# MCU.net
KiCad netlist of a schematic drawn in Altium Designer
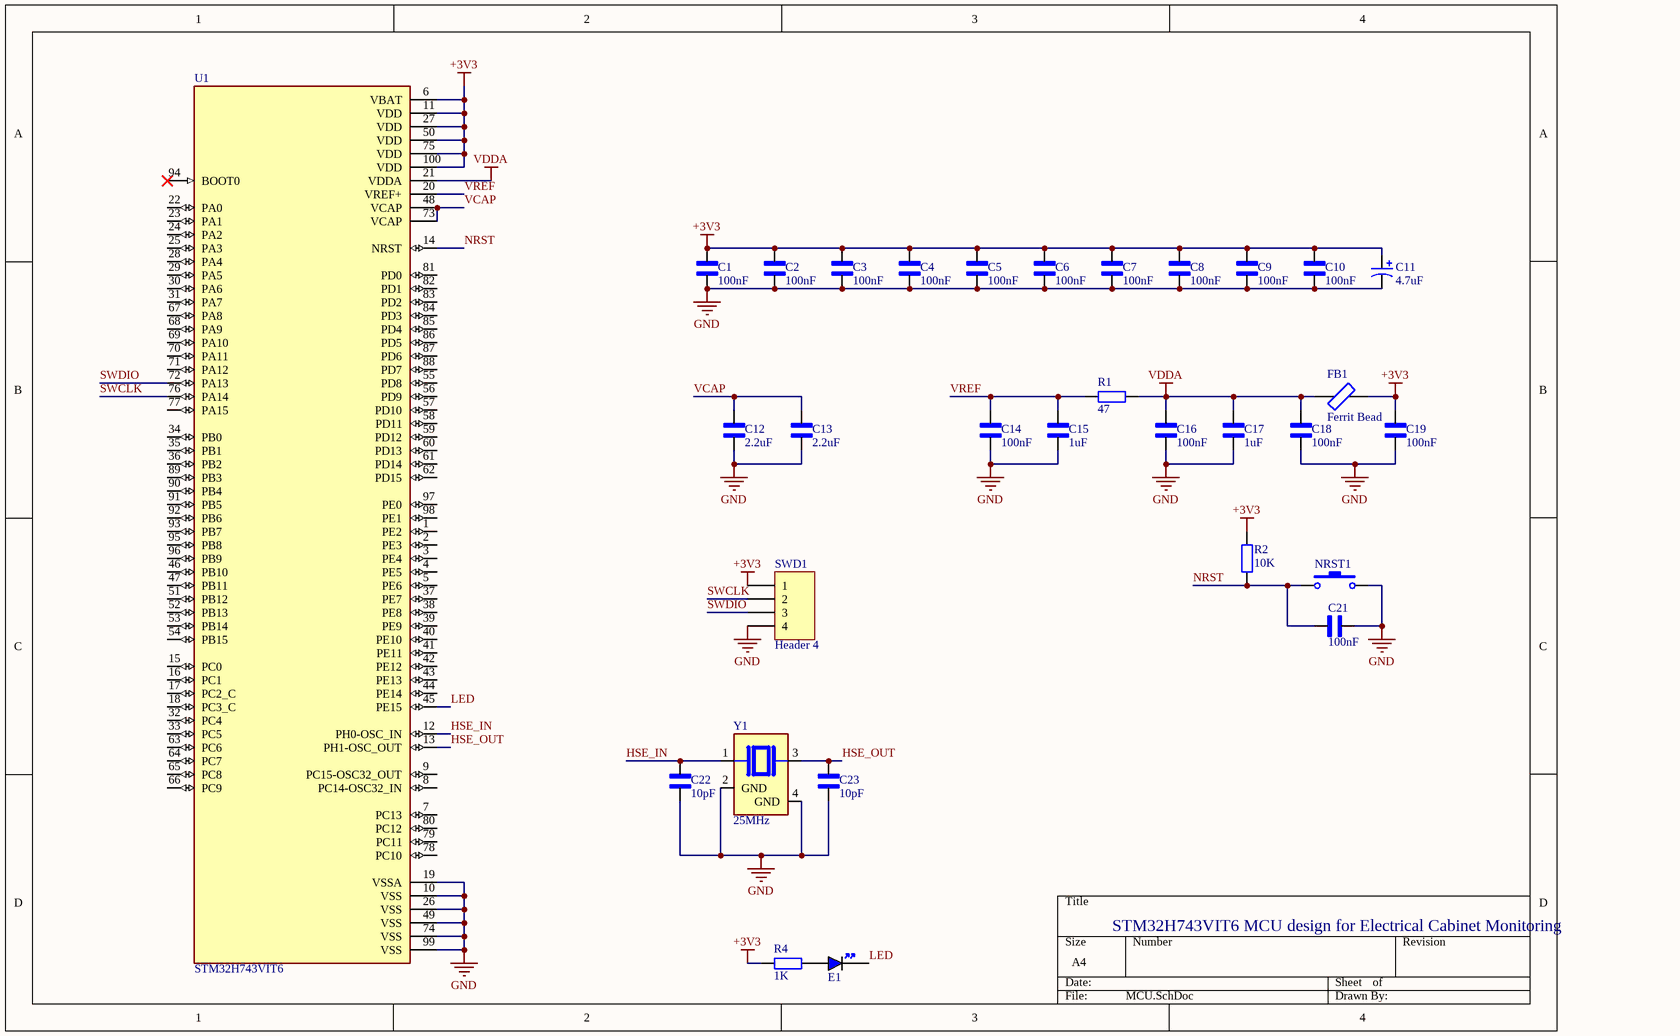
[diagram p0: MCU.SchDoc]

(export (version "E")
  (design (tool "Eeschema 10.0.6"))
  (components
    (comp (ref "C1")
      (value "100nF")
      (footprint "CAPC2012X145N")
      (description "39 pF Â±2% 200V Ceramic Capacitor C0G, NP0 0805 (2012 Metric)")
      (fields (field (name "MF") "Vishay Vitramon") (field (name "MP") "VJ0805A390GXCAP"))
      (libsource (lib "VJ0805A390GXCAP") (part "VJ0805A390GXCAP"))
    )
    (comp (ref "C2")
      (value "100nF")
      (footprint "CAPC2012X145N")
      (description "39 pF Â±2% 200V Ceramic Capacitor C0G, NP0 0805 (2012 Metric)")
      (fields (field (name "MF") "Vishay Vitramon") (field (name "MP") "VJ0805A390GXCAP"))
      (libsource (lib "VJ0805A390GXCAP") (part "VJ0805A390GXCAP"))
    )
    (comp (ref "C3")
      (value "100nF")
      (footprint "CAPC2012X145N")
      (description "39 pF Â±2% 200V Ceramic Capacitor C0G, NP0 0805 (2012 Metric)")
      (fields (field (name "MF") "Vishay Vitramon") (field (name "MP") "VJ0805A390GXCAP"))
      (libsource (lib "VJ0805A390GXCAP") (part "VJ0805A390GXCAP"))
    )
    (comp (ref "C4")
      (value "100nF")
      (footprint "CAPC2012X145N")
      (description "39 pF Â±2% 200V Ceramic Capacitor C0G, NP0 0805 (2012 Metric)")
      (fields (field (name "MF") "Vishay Vitramon") (field (name "MP") "VJ0805A390GXCAP"))
      (libsource (lib "VJ0805A390GXCAP") (part "VJ0805A390GXCAP"))
    )
    (comp (ref "C5")
      (value "100nF")
      (footprint "CAPC2012X145N")
      (description "39 pF Â±2% 200V Ceramic Capacitor C0G, NP0 0805 (2012 Metric)")
      (fields (field (name "MF") "Vishay Vitramon") (field (name "MP") "VJ0805A390GXCAP"))
      (libsource (lib "VJ0805A390GXCAP") (part "VJ0805A390GXCAP"))
    )
    (comp (ref "C6")
      (value "100nF")
      (footprint "CAPC2012X145N")
      (description "39 pF Â±2% 200V Ceramic Capacitor C0G, NP0 0805 (2012 Metric)")
      (fields (field (name "MF") "Vishay Vitramon") (field (name "MP") "VJ0805A390GXCAP"))
      (libsource (lib "VJ0805A390GXCAP") (part "VJ0805A390GXCAP"))
    )
    (comp (ref "C7")
      (value "100nF")
      (footprint "CAPC2012X145N")
      (description "39 pF Â±2% 200V Ceramic Capacitor C0G, NP0 0805 (2012 Metric)")
      (fields (field (name "MF") "Vishay Vitramon") (field (name "MP") "VJ0805A390GXCAP"))
      (libsource (lib "VJ0805A390GXCAP") (part "VJ0805A390GXCAP"))
    )
    (comp (ref "C8")
      (value "100nF")
      (footprint "CAPC2012X145N")
      (description "39 pF Â±2% 200V Ceramic Capacitor C0G, NP0 0805 (2012 Metric)")
      (fields (field (name "MF") "Vishay Vitramon") (field (name "MP") "VJ0805A390GXCAP"))
      (libsource (lib "VJ0805A390GXCAP") (part "VJ0805A390GXCAP"))
    )
    (comp (ref "C9")
      (value "100nF")
      (footprint "CAPC2012X145N")
      (description "39 pF Â±2% 200V Ceramic Capacitor C0G, NP0 0805 (2012 Metric)")
      (fields (field (name "MF") "Vishay Vitramon") (field (name "MP") "VJ0805A390GXCAP"))
      (libsource (lib "VJ0805A390GXCAP") (part "VJ0805A390GXCAP"))
    )
    (comp (ref "C10")
      (value "100nF")
      (footprint "CAPC2012X145N")
      (description "39 pF Â±2% 200V Ceramic Capacitor C0G, NP0 0805 (2012 Metric)")
      (fields (field (name "MF") "Vishay Vitramon") (field (name "MP") "VJ0805A390GXCAP"))
      (libsource (lib "VJ0805A390GXCAP") (part "VJ0805A390GXCAP"))
    )
    (comp (ref "C11")
      (value "4.7uF")
      (footprint "CAPC2012X145N")
      (description "Polazied Tantalum Capacitor")
      (libsource (lib "My Library") (part "CAP_TAN_SMD"))
    )
    (comp (ref "C12")
      (value "2.2uF")
      (footprint "CAPC2012X145N")
      (description "39 pF Â±2% 200V Ceramic Capacitor C0G, NP0 0805 (2012 Metric)")
      (fields (field (name "MF") "Vishay Vitramon") (field (name "MP") "VJ0805A390GXCAP"))
      (libsource (lib "VJ0805A390GXCAP") (part "VJ0805A390GXCAP"))
    )
    (comp (ref "C13")
      (value "2.2uF")
      (footprint "CAPC2012X145N")
      (description "39 pF Â±2% 200V Ceramic Capacitor C0G, NP0 0805 (2012 Metric)")
      (fields (field (name "MF") "Vishay Vitramon") (field (name "MP") "VJ0805A390GXCAP"))
      (libsource (lib "VJ0805A390GXCAP") (part "VJ0805A390GXCAP"))
    )
    (comp (ref "C14")
      (value "100nF")
      (footprint "CAPC2012X145N")
      (description "39 pF Â±2% 200V Ceramic Capacitor C0G, NP0 0805 (2012 Metric)")
      (fields (field (name "MF") "Vishay Vitramon") (field (name "MP") "VJ0805A390GXCAP"))
      (libsource (lib "VJ0805A390GXCAP") (part "VJ0805A390GXCAP"))
    )
    (comp (ref "C15")
      (value "1uF")
      (footprint "CAPC2012X145N")
      (description "39 pF Â±2% 200V Ceramic Capacitor C0G, NP0 0805 (2012 Metric)")
      (fields (field (name "MF") "Vishay Vitramon") (field (name "MP") "VJ0805A390GXCAP"))
      (libsource (lib "VJ0805A390GXCAP") (part "VJ0805A390GXCAP"))
    )
    (comp (ref "C16")
      (value "100nF")
      (footprint "CAPC2012X145N")
      (description "39 pF Â±2% 200V Ceramic Capacitor C0G, NP0 0805 (2012 Metric)")
      (fields (field (name "MF") "Vishay Vitramon") (field (name "MP") "VJ0805A390GXCAP"))
      (libsource (lib "VJ0805A390GXCAP") (part "VJ0805A390GXCAP"))
    )
    (comp (ref "C17")
      (value "1uF")
      (footprint "CAPC2012X145N")
      (description "39 pF Â±2% 200V Ceramic Capacitor C0G, NP0 0805 (2012 Metric)")
      (fields (field (name "MF") "Vishay Vitramon") (field (name "MP") "VJ0805A390GXCAP"))
      (libsource (lib "VJ0805A390GXCAP") (part "VJ0805A390GXCAP"))
    )
    (comp (ref "C18")
      (value "100nF")
      (footprint "CAPC2012X145N")
      (description "39 pF Â±2% 200V Ceramic Capacitor C0G, NP0 0805 (2012 Metric)")
      (fields (field (name "MF") "Vishay Vitramon") (field (name "MP") "VJ0805A390GXCAP"))
      (libsource (lib "VJ0805A390GXCAP") (part "VJ0805A390GXCAP"))
    )
    (comp (ref "C19")
      (value "100nF")
      (footprint "CAPC2012X145N")
      (description "39 pF Â±2% 200V Ceramic Capacitor C0G, NP0 0805 (2012 Metric)")
      (fields (field (name "MF") "Vishay Vitramon") (field (name "MP") "VJ0805A390GXCAP"))
      (libsource (lib "VJ0805A390GXCAP") (part "VJ0805A390GXCAP"))
    )
    (comp (ref "C21")
      (value "100nF")
      (footprint "CAPC2012X145N")
      (description "39 pF Â±2% 200V Ceramic Capacitor C0G, NP0 0805 (2012 Metric)")
      (fields (field (name "MF") "Vishay Vitramon") (field (name "MP") "VJ0805A390GXCAP"))
      (libsource (lib "") (part "VJ0805A390GXCAP_1"))
    )
    (comp (ref "C22")
      (value "10pF")
      (footprint "CAPC2012X145N")
      (description "39 pF Â±2% 200V Ceramic Capacitor C0G, NP0 0805 (2012 Metric)")
      (fields (field (name "MF") "Vishay Vitramon") (field (name "MP") "VJ0805A390GXCAP"))
      (libsource (lib "VJ0805A390GXCAP") (part "VJ0805A390GXCAP"))
    )
    (comp (ref "C23")
      (value "10pF")
      (footprint "CAPC2012X145N")
      (description "39 pF Â±2% 200V Ceramic Capacitor C0G, NP0 0805 (2012 Metric)")
      (fields (field (name "MF") "Vishay Vitramon") (field (name "MP") "VJ0805A390GXCAP"))
      (libsource (lib "VJ0805A390GXCAP") (part "VJ0805A390GXCAP"))
    )
    (comp (ref "E1")
      (value "BLUE")
      (footprint "LED_0805_BLUE")
      (description "LED 0805 BLUE SMD")
      (libsource (lib "Schematic-Lib-PhilsLab") (part "LED_0805_BLUE"))
    )
    (comp (ref "FB1")
      (value "Ferrit Bead")
      (footprint "RES-SMD-0805")
      (description "Generic Ferrit Bead")
      (libsource (lib "My Library") (part "Ferrit Bead"))
    )
    (comp (ref "NRST1")
      (value "SW-SMD")
      (footprint "SW-SMD")
      (description "Switch")
      (fields (field (name "PUBLISHER") "Altium Limited"))
      (libsource (lib "My Library") (part "SW-SMD"))
    )
    (comp (ref "R1")
      (value "47")
      (footprint "SM-0805")
      (description "Resistor SMD")
      (libsource (lib "My Library") (part "RM"))
    )
    (comp (ref "R2")
      (value "10K")
      (footprint "SM-0805")
      (description "Resistor SMD")
      (libsource (lib "My Library") (part "RM"))
    )
    (comp (ref "R4")
      (value "1K")
      (footprint "SM-0805")
      (description "Resistor SMD")
      (libsource (lib "My Library") (part "RM"))
    )
    (comp (ref "SWD1")
      (value "Header 4")
      (footprint "HDR1X4")
      (description "Header, 4-Pin")
      (fields (field (name "PUBLISHER") "Altium Limited"))
      (libsource (lib "My Library") (part "Header 4"))
    )
    (comp (ref "U1")
      (value "STM32H743VIT6")
      (footprint "QFP50P1600X1600X160-100N")
      (fields (field (name "MF") "STMicroelectronics"))
      (libsource (lib "STM32H743VIT6") (part "STM32H743VIT6"))
    )
    (comp (ref "Y1")
      (value "25MHz")
      (footprint "XTAL_ABM8G-25.000MHZ-B4Y-T")
      (description "25 MHz Â±30ppm Crystal 10pF 60 Ohms 4-SMD, No Lead")
      (fields (field (name "MP") "ABM8G-25.000MHZ-B4Y-T") (field (name "MF") "Abracon"))
      (libsource (lib "My Library") (part "ABM8G-25.000MHZ-B4Y-T"))
    )
  )
  (nets
    (net (code "1") (name "+3V3") (class "Default")
      (node (ref "C1") (pin "2") (pinfunction "2_2") (pintype "passive"))
      (node (ref "C10") (pin "2") (pinfunction "2_2") (pintype "passive"))
      (node (ref "C11") (pin "2") (pinfunction "2_2") (pintype "passive"))
      (node (ref "C19") (pin "2") (pinfunction "2_2") (pintype "passive"))
      (node (ref "C2") (pin "2") (pinfunction "2_2") (pintype "passive"))
      (node (ref "C3") (pin "2") (pinfunction "2_2") (pintype "passive"))
      (node (ref "C4") (pin "2") (pinfunction "2_2") (pintype "passive"))
      (node (ref "C5") (pin "2") (pinfunction "2_2") (pintype "passive"))
      (node (ref "C6") (pin "2") (pinfunction "2_2") (pintype "passive"))
      (node (ref "C7") (pin "2") (pinfunction "2_2") (pintype "passive"))
      (node (ref "C8") (pin "2") (pinfunction "2_2") (pintype "passive"))
      (node (ref "C9") (pin "2") (pinfunction "2_2") (pintype "passive"))
      (node (ref "FB1") (pin "2") (pintype "passive"))
      (node (ref "R2") (pin "2") (pinfunction "2_2") (pintype "passive"))
      (node (ref "R4") (pin "1") (pinfunction "1_1") (pintype "passive"))
      (node (ref "SWD1") (pin "1") (pinfunction "1_1") (pintype "passive"))
      (node (ref "U1") (pin "100") (pinfunction "VDD_100") (pintype "power_in"))
      (node (ref "U1") (pin "11") (pinfunction "VDD_11") (pintype "power_in"))
      (node (ref "U1") (pin "27") (pinfunction "VDD_27") (pintype "power_in"))
      (node (ref "U1") (pin "50") (pinfunction "VDD_50") (pintype "power_in"))
      (node (ref "U1") (pin "6") (pinfunction "VBAT_6") (pintype "power_in"))
      (node (ref "U1") (pin "75") (pinfunction "VDD_75") (pintype "power_in"))
    )
    (net (code "2") (name "/HSE_IN") (class "Default")
      (node (ref "C22") (pin "2") (pinfunction "2_2") (pintype "passive"))
      (node (ref "U1") (pin "12") (pinfunction "PH0-OSC_IN_12") (pintype "bidirectional"))
      (node (ref "Y1") (pin "1") (pinfunction "1_1") (pintype "passive"))
    )
    (net (code "3") (name "/HSE_OUT") (class "Default")
      (node (ref "C23") (pin "2") (pinfunction "2_2") (pintype "passive"))
      (node (ref "U1") (pin "13") (pinfunction "PH1-OSC_OUT_13") (pintype "bidirectional"))
      (node (ref "Y1") (pin "3") (pinfunction "2_3") (pintype "passive"))
    )
    (net (code "4") (name "/LED") (class "Default")
      (node (ref "E1") (pin "K") (pinfunction "K_K") (pintype "passive"))
      (node (ref "U1") (pin "45") (pinfunction "PE15_45") (pintype "bidirectional"))
    )
    (net (code "5") (name "/NRST") (class "Default")
      (node (ref "C21") (pin "2") (pinfunction "2_2") (pintype "passive"))
      (node (ref "NRST1") (pin "1") (pinfunction "1_1") (pintype "passive"))
      (node (ref "R2") (pin "1") (pinfunction "1_1") (pintype "passive"))
      (node (ref "U1") (pin "14") (pinfunction "NRST_14") (pintype "bidirectional"))
    )
    (net (code "6") (name "/SWCLK") (class "Default")
      (node (ref "SWD1") (pin "2") (pinfunction "2_2") (pintype "passive"))
      (node (ref "U1") (pin "76") (pinfunction "PA14_76") (pintype "bidirectional"))
    )
    (net (code "7") (name "/SWDIO") (class "Default")
      (node (ref "SWD1") (pin "3") (pinfunction "3_3") (pintype "passive"))
      (node (ref "U1") (pin "72") (pinfunction "PA13_72") (pintype "bidirectional"))
    )
    (net (code "8") (name "/VCAP") (class "Default")
      (node (ref "C12") (pin "2") (pinfunction "2_2") (pintype "passive"))
      (node (ref "C13") (pin "2") (pinfunction "2_2") (pintype "passive"))
      (node (ref "U1") (pin "48") (pinfunction "VCAP_48") (pintype "power_in"))
      (node (ref "U1") (pin "73") (pinfunction "VCAP_73") (pintype "power_in"))
    )
    (net (code "9") (name "/VREF") (class "Default")
      (node (ref "C14") (pin "2") (pinfunction "2_2") (pintype "passive"))
      (node (ref "C15") (pin "2") (pinfunction "2_2") (pintype "passive"))
      (node (ref "R1") (pin "1") (pinfunction "1_1") (pintype "passive"))
      (node (ref "U1") (pin "20") (pinfunction "VREF+_20") (pintype "power_in"))
    )
    (net (code "10") (name "GND") (class "Default")
      (node (ref "C1") (pin "1") (pinfunction "1_1") (pintype "passive"))
      (node (ref "C10") (pin "1") (pinfunction "1_1") (pintype "passive"))
      (node (ref "C11") (pin "1") (pinfunction "1_1") (pintype "passive"))
      (node (ref "C12") (pin "1") (pinfunction "1_1") (pintype "passive"))
      (node (ref "C13") (pin "1") (pinfunction "1_1") (pintype "passive"))
      (node (ref "C14") (pin "1") (pinfunction "1_1") (pintype "passive"))
      (node (ref "C15") (pin "1") (pinfunction "1_1") (pintype "passive"))
      (node (ref "C16") (pin "1") (pinfunction "1_1") (pintype "passive"))
      (node (ref "C17") (pin "1") (pinfunction "1_1") (pintype "passive"))
      (node (ref "C18") (pin "1") (pinfunction "1_1") (pintype "passive"))
      (node (ref "C19") (pin "1") (pinfunction "1_1") (pintype "passive"))
      (node (ref "C2") (pin "1") (pinfunction "1_1") (pintype "passive"))
      (node (ref "C21") (pin "1") (pinfunction "1_1") (pintype "passive"))
      (node (ref "C22") (pin "1") (pinfunction "1_1") (pintype "passive"))
      (node (ref "C23") (pin "1") (pinfunction "1_1") (pintype "passive"))
      (node (ref "C3") (pin "1") (pinfunction "1_1") (pintype "passive"))
      (node (ref "C4") (pin "1") (pinfunction "1_1") (pintype "passive"))
      (node (ref "C5") (pin "1") (pinfunction "1_1") (pintype "passive"))
      (node (ref "C6") (pin "1") (pinfunction "1_1") (pintype "passive"))
      (node (ref "C7") (pin "1") (pinfunction "1_1") (pintype "passive"))
      (node (ref "C8") (pin "1") (pinfunction "1_1") (pintype "passive"))
      (node (ref "C9") (pin "1") (pinfunction "1_1") (pintype "passive"))
      (node (ref "NRST1") (pin "2") (pinfunction "2_2") (pintype "passive"))
      (node (ref "SWD1") (pin "4") (pinfunction "4_4") (pintype "passive"))
      (node (ref "U1") (pin "10") (pinfunction "VSS_10") (pintype "power_in"))
      (node (ref "U1") (pin "19") (pinfunction "VSSA_19") (pintype "power_in"))
      (node (ref "U1") (pin "26") (pinfunction "VSS_26") (pintype "power_in"))
      (node (ref "U1") (pin "49") (pinfunction "VSS_49") (pintype "power_in"))
      (node (ref "U1") (pin "74") (pinfunction "VSS_74") (pintype "power_in"))
      (node (ref "U1") (pin "99") (pinfunction "VSS_99") (pintype "power_in"))
      (node (ref "Y1") (pin "2") (pinfunction "GND_2") (pintype "power_in"))
      (node (ref "Y1") (pin "4") (pinfunction "GND_4") (pintype "power_in"))
    )
    (net (code "11") (name "Net-(E1-PadA)") (class "Default")
      (node (ref "E1") (pin "A") (pinfunction "A_A") (pintype "passive"))
      (node (ref "R4") (pin "2") (pinfunction "2_2") (pintype "passive"))
    )
    (net (code "12") (name "VDDA") (class "Default")
      (node (ref "C16") (pin "2") (pinfunction "2_2") (pintype "passive"))
      (node (ref "C17") (pin "2") (pinfunction "2_2") (pintype "passive"))
      (node (ref "C18") (pin "2") (pinfunction "2_2") (pintype "passive"))
      (node (ref "FB1") (pin "1") (pintype "passive"))
      (node (ref "R1") (pin "2") (pinfunction "2_2") (pintype "passive"))
      (node (ref "U1") (pin "21") (pinfunction "VDDA_21") (pintype "power_in"))
    )
    (net (code "13") (name "unconnected-(U1-BOOT0-Pad94)") (class "Default")
      (node (ref "U1") (pin "94") (pinfunction "BOOT0_94") (pintype "input+no_connect"))
    )
    (net (code "14") (name "unconnected-(U1-PA0-Pad22)") (class "Default")
      (node (ref "U1") (pin "22") (pinfunction "PA0_22") (pintype "bidirectional"))
    )
    (net (code "15") (name "unconnected-(U1-PA1-Pad23)") (class "Default")
      (node (ref "U1") (pin "23") (pinfunction "PA1_23") (pintype "bidirectional"))
    )
    (net (code "16") (name "unconnected-(U1-PA2-Pad24)") (class "Default")
      (node (ref "U1") (pin "24") (pinfunction "PA2_24") (pintype "bidirectional"))
    )
    (net (code "17") (name "unconnected-(U1-PA3-Pad25)") (class "Default")
      (node (ref "U1") (pin "25") (pinfunction "PA3_25") (pintype "bidirectional"))
    )
    (net (code "18") (name "unconnected-(U1-PA4-Pad28)") (class "Default")
      (node (ref "U1") (pin "28") (pinfunction "PA4_28") (pintype "bidirectional"))
    )
    (net (code "19") (name "unconnected-(U1-PA5-Pad29)") (class "Default")
      (node (ref "U1") (pin "29") (pinfunction "PA5_29") (pintype "bidirectional"))
    )
    (net (code "20") (name "unconnected-(U1-PA6-Pad30)") (class "Default")
      (node (ref "U1") (pin "30") (pinfunction "PA6_30") (pintype "bidirectional"))
    )
    (net (code "21") (name "unconnected-(U1-PA7-Pad31)") (class "Default")
      (node (ref "U1") (pin "31") (pinfunction "PA7_31") (pintype "bidirectional"))
    )
    (net (code "22") (name "unconnected-(U1-PA8-Pad67)") (class "Default")
      (node (ref "U1") (pin "67") (pinfunction "PA8_67") (pintype "bidirectional"))
    )
    (net (code "23") (name "unconnected-(U1-PA9-Pad68)") (class "Default")
      (node (ref "U1") (pin "68") (pinfunction "PA9_68") (pintype "bidirectional"))
    )
    (net (code "24") (name "unconnected-(U1-PA10-Pad69)") (class "Default")
      (node (ref "U1") (pin "69") (pinfunction "PA10_69") (pintype "bidirectional"))
    )
    (net (code "25") (name "unconnected-(U1-PA11-Pad70)") (class "Default")
      (node (ref "U1") (pin "70") (pinfunction "PA11_70") (pintype "bidirectional"))
    )
    (net (code "26") (name "unconnected-(U1-PA12-Pad71)") (class "Default")
      (node (ref "U1") (pin "71") (pinfunction "PA12_71") (pintype "bidirectional"))
    )
    (net (code "27") (name "unconnected-(U1-PA15-Pad77)") (class "Default")
      (node (ref "U1") (pin "77") (pinfunction "PA15_77") (pintype "bidirectional"))
    )
    (net (code "28") (name "unconnected-(U1-PB0-Pad34)") (class "Default")
      (node (ref "U1") (pin "34") (pinfunction "PB0_34") (pintype "bidirectional"))
    )
    (net (code "29") (name "unconnected-(U1-PB1-Pad35)") (class "Default")
      (node (ref "U1") (pin "35") (pinfunction "PB1_35") (pintype "bidirectional"))
    )
    (net (code "30") (name "unconnected-(U1-PB2-Pad36)") (class "Default")
      (node (ref "U1") (pin "36") (pinfunction "PB2_36") (pintype "bidirectional"))
    )
    (net (code "31") (name "unconnected-(U1-PB3-Pad89)") (class "Default")
      (node (ref "U1") (pin "89") (pinfunction "PB3_89") (pintype "bidirectional"))
    )
    (net (code "32") (name "unconnected-(U1-PB4-Pad90)") (class "Default")
      (node (ref "U1") (pin "90") (pinfunction "PB4_90") (pintype "bidirectional"))
    )
    (net (code "33") (name "unconnected-(U1-PB5-Pad91)") (class "Default")
      (node (ref "U1") (pin "91") (pinfunction "PB5_91") (pintype "bidirectional"))
    )
    (net (code "34") (name "unconnected-(U1-PB6-Pad92)") (class "Default")
      (node (ref "U1") (pin "92") (pinfunction "PB6_92") (pintype "bidirectional"))
    )
    (net (code "35") (name "unconnected-(U1-PB7-Pad93)") (class "Default")
      (node (ref "U1") (pin "93") (pinfunction "PB7_93") (pintype "bidirectional"))
    )
    (net (code "36") (name "unconnected-(U1-PB8-Pad95)") (class "Default")
      (node (ref "U1") (pin "95") (pinfunction "PB8_95") (pintype "bidirectional"))
    )
    (net (code "37") (name "unconnected-(U1-PB9-Pad96)") (class "Default")
      (node (ref "U1") (pin "96") (pinfunction "PB9_96") (pintype "bidirectional"))
    )
    (net (code "38") (name "unconnected-(U1-PB10-Pad46)") (class "Default")
      (node (ref "U1") (pin "46") (pinfunction "PB10_46") (pintype "bidirectional"))
    )
    (net (code "39") (name "unconnected-(U1-PB11-Pad47)") (class "Default")
      (node (ref "U1") (pin "47") (pinfunction "PB11_47") (pintype "bidirectional"))
    )
    (net (code "40") (name "unconnected-(U1-PB12-Pad51)") (class "Default")
      (node (ref "U1") (pin "51") (pinfunction "PB12_51") (pintype "bidirectional"))
    )
    (net (code "41") (name "unconnected-(U1-PB13-Pad52)") (class "Default")
      (node (ref "U1") (pin "52") (pinfunction "PB13_52") (pintype "bidirectional"))
    )
    (net (code "42") (name "unconnected-(U1-PB14-Pad53)") (class "Default")
      (node (ref "U1") (pin "53") (pinfunction "PB14_53") (pintype "bidirectional"))
    )
    (net (code "43") (name "unconnected-(U1-PB15-Pad54)") (class "Default")
      (node (ref "U1") (pin "54") (pinfunction "PB15_54") (pintype "bidirectional"))
    )
    (net (code "44") (name "unconnected-(U1-PC0-Pad15)") (class "Default")
      (node (ref "U1") (pin "15") (pinfunction "PC0_15") (pintype "bidirectional"))
    )
    (net (code "45") (name "unconnected-(U1-PC1-Pad16)") (class "Default")
      (node (ref "U1") (pin "16") (pinfunction "PC1_16") (pintype "bidirectional"))
    )
    (net (code "46") (name "unconnected-(U1-PC2_C-Pad17)") (class "Default")
      (node (ref "U1") (pin "17") (pinfunction "PC2_C_17") (pintype "bidirectional"))
    )
    (net (code "47") (name "unconnected-(U1-PC3_C-Pad18)") (class "Default")
      (node (ref "U1") (pin "18") (pinfunction "PC3_C_18") (pintype "bidirectional"))
    )
    (net (code "48") (name "unconnected-(U1-PC4-Pad32)") (class "Default")
      (node (ref "U1") (pin "32") (pinfunction "PC4_32") (pintype "bidirectional"))
    )
    (net (code "49") (name "unconnected-(U1-PC5-Pad33)") (class "Default")
      (node (ref "U1") (pin "33") (pinfunction "PC5_33") (pintype "bidirectional"))
    )
    (net (code "50") (name "unconnected-(U1-PC6-Pad63)") (class "Default")
      (node (ref "U1") (pin "63") (pinfunction "PC6_63") (pintype "bidirectional"))
    )
    (net (code "51") (name "unconnected-(U1-PC7-Pad64)") (class "Default")
      (node (ref "U1") (pin "64") (pinfunction "PC7_64") (pintype "bidirectional"))
    )
    (net (code "52") (name "unconnected-(U1-PC8-Pad65)") (class "Default")
      (node (ref "U1") (pin "65") (pinfunction "PC8_65") (pintype "bidirectional"))
    )
    (net (code "53") (name "unconnected-(U1-PC9-Pad66)") (class "Default")
      (node (ref "U1") (pin "66") (pinfunction "PC9_66") (pintype "bidirectional"))
    )
    (net (code "54") (name "unconnected-(U1-PC10-Pad78)") (class "Default")
      (node (ref "U1") (pin "78") (pinfunction "PC10_78") (pintype "bidirectional"))
    )
    (net (code "55") (name "unconnected-(U1-PC11-Pad79)") (class "Default")
      (node (ref "U1") (pin "79") (pinfunction "PC11_79") (pintype "bidirectional"))
    )
    (net (code "56") (name "unconnected-(U1-PC12-Pad80)") (class "Default")
      (node (ref "U1") (pin "80") (pinfunction "PC12_80") (pintype "bidirectional"))
    )
    (net (code "57") (name "unconnected-(U1-PC13-Pad7)") (class "Default")
      (node (ref "U1") (pin "7") (pinfunction "PC13_7") (pintype "bidirectional"))
    )
    (net (code "58") (name "unconnected-(U1-PC14-OSC32_IN-Pad8)") (class "Default")
      (node (ref "U1") (pin "8") (pinfunction "PC14-OSC32_IN_8") (pintype "bidirectional"))
    )
    (net (code "59") (name "unconnected-(U1-PC15-OSC32_OUT-Pad9)") (class "Default")
      (node (ref "U1") (pin "9") (pinfunction "PC15-OSC32_OUT_9") (pintype "bidirectional"))
    )
    (net (code "60") (name "unconnected-(U1-PD0-Pad81)") (class "Default")
      (node (ref "U1") (pin "81") (pinfunction "PD0_81") (pintype "bidirectional"))
    )
    (net (code "61") (name "unconnected-(U1-PD1-Pad82)") (class "Default")
      (node (ref "U1") (pin "82") (pinfunction "PD1_82") (pintype "bidirectional"))
    )
    (net (code "62") (name "unconnected-(U1-PD2-Pad83)") (class "Default")
      (node (ref "U1") (pin "83") (pinfunction "PD2_83") (pintype "bidirectional"))
    )
    (net (code "63") (name "unconnected-(U1-PD3-Pad84)") (class "Default")
      (node (ref "U1") (pin "84") (pinfunction "PD3_84") (pintype "bidirectional"))
    )
    (net (code "64") (name "unconnected-(U1-PD4-Pad85)") (class "Default")
      (node (ref "U1") (pin "85") (pinfunction "PD4_85") (pintype "bidirectional"))
    )
    (net (code "65") (name "unconnected-(U1-PD5-Pad86)") (class "Default")
      (node (ref "U1") (pin "86") (pinfunction "PD5_86") (pintype "bidirectional"))
    )
    (net (code "66") (name "unconnected-(U1-PD6-Pad87)") (class "Default")
      (node (ref "U1") (pin "87") (pinfunction "PD6_87") (pintype "bidirectional"))
    )
    (net (code "67") (name "unconnected-(U1-PD7-Pad88)") (class "Default")
      (node (ref "U1") (pin "88") (pinfunction "PD7_88") (pintype "bidirectional"))
    )
    (net (code "68") (name "unconnected-(U1-PD8-Pad55)") (class "Default")
      (node (ref "U1") (pin "55") (pinfunction "PD8_55") (pintype "bidirectional"))
    )
    (net (code "69") (name "unconnected-(U1-PD9-Pad56)") (class "Default")
      (node (ref "U1") (pin "56") (pinfunction "PD9_56") (pintype "bidirectional"))
    )
    (net (code "70") (name "unconnected-(U1-PD10-Pad57)") (class "Default")
      (node (ref "U1") (pin "57") (pinfunction "PD10_57") (pintype "bidirectional"))
    )
    (net (code "71") (name "unconnected-(U1-PD11-Pad58)") (class "Default")
      (node (ref "U1") (pin "58") (pinfunction "PD11_58") (pintype "bidirectional"))
    )
    (net (code "72") (name "unconnected-(U1-PD12-Pad59)") (class "Default")
      (node (ref "U1") (pin "59") (pinfunction "PD12_59") (pintype "bidirectional"))
    )
    (net (code "73") (name "unconnected-(U1-PD13-Pad60)") (class "Default")
      (node (ref "U1") (pin "60") (pinfunction "PD13_60") (pintype "bidirectional"))
    )
    (net (code "74") (name "unconnected-(U1-PD14-Pad61)") (class "Default")
      (node (ref "U1") (pin "61") (pinfunction "PD14_61") (pintype "bidirectional"))
    )
    (net (code "75") (name "unconnected-(U1-PD15-Pad62)") (class "Default")
      (node (ref "U1") (pin "62") (pinfunction "PD15_62") (pintype "bidirectional"))
    )
    (net (code "76") (name "unconnected-(U1-PE0-Pad97)") (class "Default")
      (node (ref "U1") (pin "97") (pinfunction "PE0_97") (pintype "bidirectional"))
    )
    (net (code "77") (name "unconnected-(U1-PE1-Pad98)") (class "Default")
      (node (ref "U1") (pin "98") (pinfunction "PE1_98") (pintype "bidirectional"))
    )
    (net (code "78") (name "unconnected-(U1-PE2-Pad1)") (class "Default")
      (node (ref "U1") (pin "1") (pinfunction "PE2_1") (pintype "bidirectional"))
    )
    (net (code "79") (name "unconnected-(U1-PE3-Pad2)") (class "Default")
      (node (ref "U1") (pin "2") (pinfunction "PE3_2") (pintype "bidirectional"))
    )
    (net (code "80") (name "unconnected-(U1-PE4-Pad3)") (class "Default")
      (node (ref "U1") (pin "3") (pinfunction "PE4_3") (pintype "bidirectional"))
    )
    (net (code "81") (name "unconnected-(U1-PE5-Pad4)") (class "Default")
      (node (ref "U1") (pin "4") (pinfunction "PE5_4") (pintype "bidirectional"))
    )
    (net (code "82") (name "unconnected-(U1-PE6-Pad5)") (class "Default")
      (node (ref "U1") (pin "5") (pinfunction "PE6_5") (pintype "bidirectional"))
    )
    (net (code "83") (name "unconnected-(U1-PE7-Pad37)") (class "Default")
      (node (ref "U1") (pin "37") (pinfunction "PE7_37") (pintype "bidirectional"))
    )
    (net (code "84") (name "unconnected-(U1-PE8-Pad38)") (class "Default")
      (node (ref "U1") (pin "38") (pinfunction "PE8_38") (pintype "bidirectional"))
    )
    (net (code "85") (name "unconnected-(U1-PE9-Pad39)") (class "Default")
      (node (ref "U1") (pin "39") (pinfunction "PE9_39") (pintype "bidirectional"))
    )
    (net (code "86") (name "unconnected-(U1-PE10-Pad40)") (class "Default")
      (node (ref "U1") (pin "40") (pinfunction "PE10_40") (pintype "bidirectional"))
    )
    (net (code "87") (name "unconnected-(U1-PE11-Pad41)") (class "Default")
      (node (ref "U1") (pin "41") (pinfunction "PE11_41") (pintype "bidirectional"))
    )
    (net (code "88") (name "unconnected-(U1-PE12-Pad42)") (class "Default")
      (node (ref "U1") (pin "42") (pinfunction "PE12_42") (pintype "bidirectional"))
    )
    (net (code "89") (name "unconnected-(U1-PE13-Pad43)") (class "Default")
      (node (ref "U1") (pin "43") (pinfunction "PE13_43") (pintype "bidirectional"))
    )
    (net (code "90") (name "unconnected-(U1-PE14-Pad44)") (class "Default")
      (node (ref "U1") (pin "44") (pinfunction "PE14_44") (pintype "bidirectional"))
    )
  )
)
